# can.net
KiCad netlist of a schematic drawn in Altium Designer
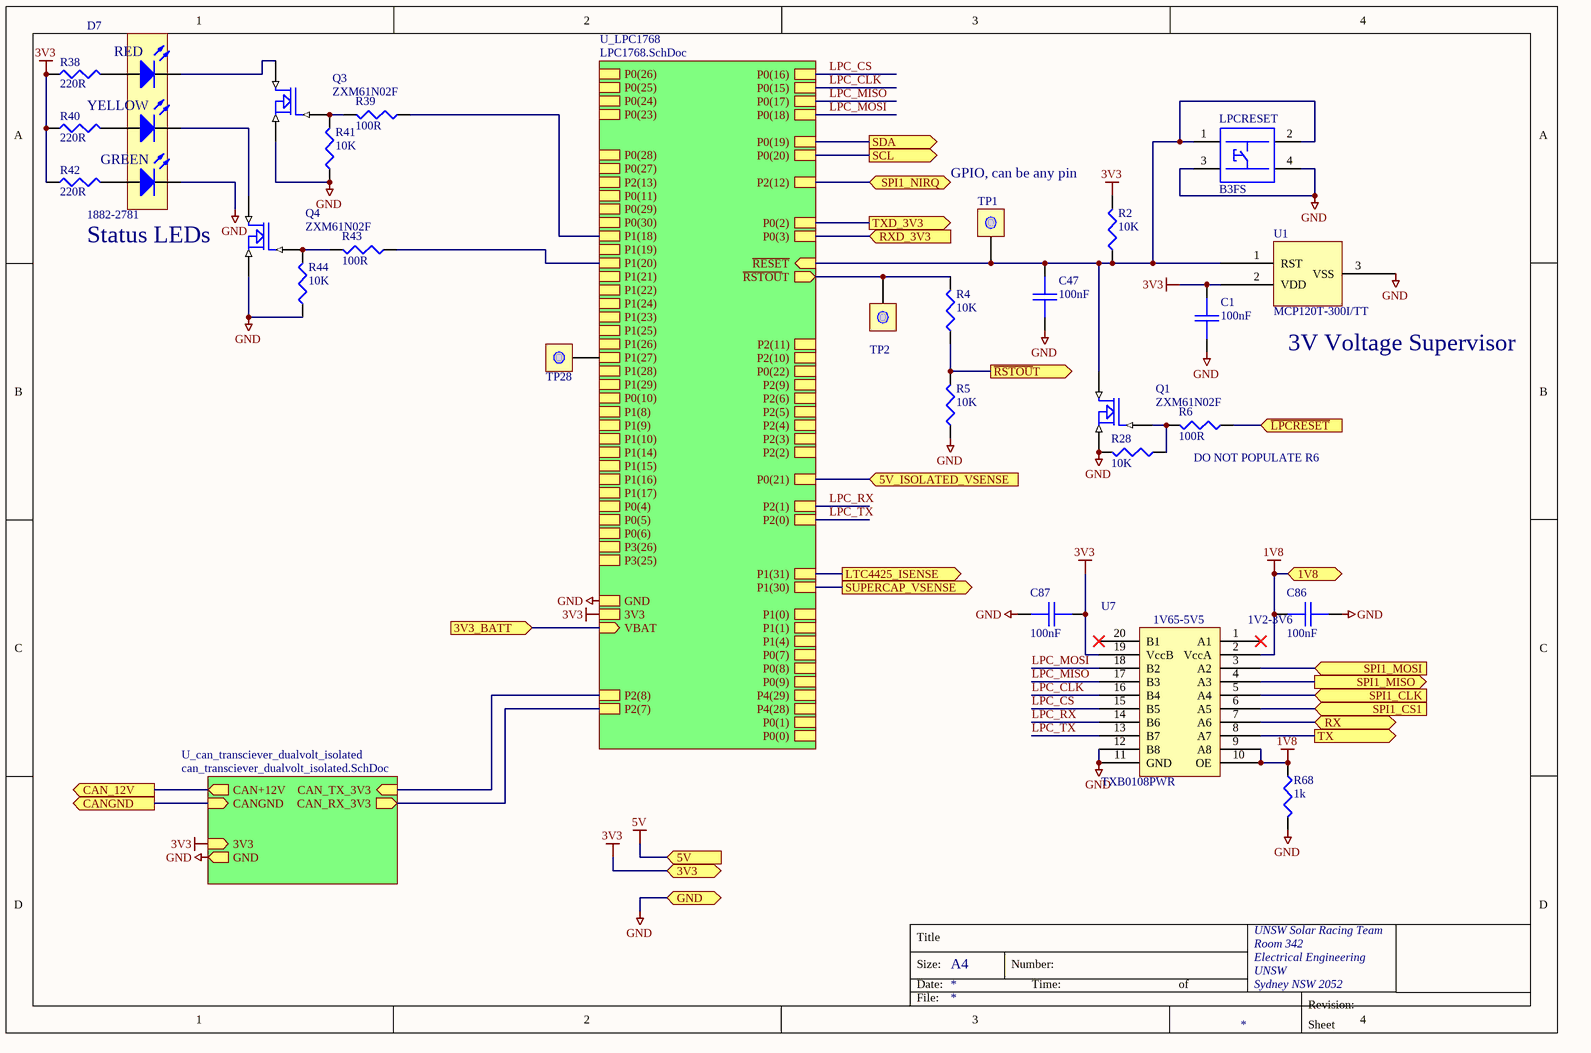
[diagram p0: can.SchDoc]

(export (version "E")
  (design (tool "Eeschema 10.0.6"))
  (components
    (comp (ref "C1")
      (value "100nF")
      (footprint "0603")
      (description "Capacitor")
      (libsource (lib "RCLDQ") (part "CAP"))
    )
    (comp (ref "C47")
      (value "100nF")
      (footprint "0603")
      (description "Capacitor")
      (libsource (lib "RCLDQ") (part "CAP"))
    )
    (comp (ref "C86")
      (value "100nF")
      (footprint "0603")
      (description "Capacitor")
      (libsource (lib "RCLDQ") (part "CAP"))
    )
    (comp (ref "C87")
      (value "100nF")
      (footprint "0603")
      (description "Capacitor")
      (libsource (lib "RCLDQ") (part "CAP"))
    )
    (comp (ref "D7")
      (value "1882-2781")
      (footprint "LED_TRILEVEL")
      (description "Three level LED")
      (libsource (lib "RCLDQ") (part "LED-TRILEVEL"))
    )
    (comp (ref "LPCRESET")
      (value "B3FS")
      (footprint "B3FS-1052")
      (description "SMD tactile switch")
      (libsource (lib "Miscellaneous") (part "B3FS"))
    )
    (comp (ref "Q1")
      (value "ZXM61N02F")
      (footprint "SOT23-3")
      (description "1.7A, 20V N-Channel Enhancement mode FET")
      (libsource (lib "RCLDQ") (part "ZXM61N02F"))
    )
    (comp (ref "Q3")
      (value "ZXM61N02F")
      (footprint "SOT23-3")
      (description "1.7A, 20V N-Channel Enhancement mode FET")
      (libsource (lib "RCLDQ") (part "ZXM61N02F"))
    )
    (comp (ref "Q4")
      (value "ZXM61N02F")
      (footprint "SOT23-3")
      (description "1.7A, 20V N-Channel Enhancement mode FET")
      (libsource (lib "RCLDQ") (part "ZXM61N02F"))
    )
    (comp (ref "R2")
      (value "10K")
      (footprint "0603")
      (description "Resistor")
      (libsource (lib "RCLDQ") (part "RES1"))
    )
    (comp (ref "R4")
      (value "10K")
      (footprint "0603")
      (description "Resistor")
      (libsource (lib "RCLDQ") (part "RES1"))
    )
    (comp (ref "R5")
      (value "10K")
      (footprint "0603")
      (description "Resistor")
      (libsource (lib "RCLDQ") (part "RES1"))
    )
    (comp (ref "R6")
      (value "100R")
      (footprint "0603")
      (description "Resistor")
      (libsource (lib "RCLDQ") (part "RES1"))
    )
    (comp (ref "R28")
      (value "10K")
      (footprint "0603")
      (description "Resistor")
      (libsource (lib "RCLDQ") (part "RES1"))
    )
    (comp (ref "R38")
      (value "220R")
      (footprint "0603")
      (description "Resistor")
      (libsource (lib "RCLDQ") (part "RES1"))
    )
    (comp (ref "R39")
      (value "100R")
      (footprint "0603")
      (description "Resistor")
      (libsource (lib "RCLDQ") (part "RES1"))
    )
    (comp (ref "R40")
      (value "220R")
      (footprint "0603")
      (description "Resistor")
      (libsource (lib "RCLDQ") (part "RES1"))
    )
    (comp (ref "R41")
      (value "10K")
      (footprint "0603")
      (description "Resistor")
      (libsource (lib "RCLDQ") (part "RES1"))
    )
    (comp (ref "R42")
      (value "220R")
      (footprint "0603")
      (description "Resistor")
      (libsource (lib "RCLDQ") (part "RES1"))
    )
    (comp (ref "R43")
      (value "100R")
      (footprint "0603")
      (description "Resistor")
      (libsource (lib "RCLDQ") (part "RES1"))
    )
    (comp (ref "R44")
      (value "10K")
      (footprint "0603")
      (description "Resistor")
      (libsource (lib "RCLDQ") (part "RES1"))
    )
    (comp (ref "R68")
      (value "1k")
      (footprint "0603")
      (description "Resistor")
      (libsource (lib "RCLDQ") (part "RES1"))
    )
    (comp (ref "TP1")
      (value "RESET")
      (footprint "TESTPOINT")
      (description "TEST POINT")
      (libsource (lib "Miscellaneous") (part "TEST"))
    )
    (comp (ref "TP2")
      (value "RSTOUT")
      (footprint "TESTPOINT")
      (description "TEST POINT")
      (libsource (lib "") (part "TEST_1"))
    )
    (comp (ref "TP28")
      (value "CLKOUT")
      (footprint "TESTPOINT")
      (description "TEST POINT")
      (libsource (lib "") (part "TEST_2"))
    )
    (comp (ref "U1")
      (value "MCP120T-300I/TT")
      (footprint "SOT23-3")
      (description "Voltage Supervisor")
      (libsource (lib "sion") (part "MCP120T"))
    )
    (comp (ref "U7")
      (value "TXB0108PWR")
      (footprint "TSSOP20")
      (description "4 bit bidirectional auto direction sense level translator")
      (libsource (lib "sion") (part "TXB0108PWR"))
    )
  )
  (nets
    (net (code "7") (name "/LPC_CLK") (class "Default")
      (node (ref "U7") (pin "16") (pinfunction "B4_16") (pintype "passive"))
    )
    (net (code "8") (name "/LPC_CS") (class "Default")
      (node (ref "U7") (pin "15") (pinfunction "B5_15") (pintype "passive"))
    )
    (net (code "9") (name "/LPC_MISO") (class "Default")
      (node (ref "U7") (pin "17") (pinfunction "B3_17") (pintype "passive"))
    )
    (net (code "10") (name "/LPC_MOSI") (class "Default")
      (node (ref "U7") (pin "18") (pinfunction "B2_18") (pintype "passive"))
    )
    (net (code "11") (name "/LPC_RX") (class "Default")
      (node (ref "U7") (pin "14") (pinfunction "B6_14") (pintype "power_in"))
    )
    (net (code "12") (name "/LPC_TX") (class "Default")
      (node (ref "U7") (pin "13") (pinfunction "B7_13") (pintype "passive"))
    )
    (net (code "43") (name "/P1(18)") (class "Default")
      (node (ref "R39") (pin "1") (pinfunction "1_1") (pintype "passive"))
    )
    (net (code "45") (name "/P1(20)") (class "Default")
      (node (ref "R43") (pin "1") (pinfunction "1_1") (pintype "passive"))
    )
    (net (code "52") (name "/P1(27)") (class "Default")
      (node (ref "TP28") (pin "0") (pinfunction "TP_0") (pintype "passive"))
    )
    (net (code "68") (name "/RX") (class "Default")
      (node (ref "U7") (pin "7") (pinfunction "A6_7") (pintype "power_in"))
    )
    (net (code "72") (name "/SPI1_CLK") (class "Default")
      (node (ref "U7") (pin "5") (pinfunction "A4_5") (pintype "passive"))
    )
    (net (code "73") (name "/SPI1_CS1") (class "Default")
      (node (ref "U7") (pin "6") (pinfunction "A5_6") (pintype "passive"))
    )
    (net (code "74") (name "/SPI1_MISO") (class "Default")
      (node (ref "U7") (pin "4") (pinfunction "A3_4") (pintype "passive"))
    )
    (net (code "75") (name "/SPI1_MOSI") (class "Default")
      (node (ref "U7") (pin "3") (pinfunction "A2_3") (pintype "passive"))
    )
    (net (code "78") (name "/TX") (class "Default")
      (node (ref "U7") (pin "8") (pinfunction "A7_8") (pintype "passive"))
    )
    (net (code "80") (name "/~{LPCRESET}") (class "Default")
      (node (ref "R6") (pin "2") (pinfunction "2_2") (pintype "passive"))
    )
    (net (code "81") (name "/~{RESET}") (class "Default")
      (node (ref "C47") (pin "1") (pinfunction "1_1") (pintype "passive"))
      (node (ref "LPCRESET") (pin "1") (pinfunction "A1_1") (pintype "passive"))
      (node (ref "LPCRESET") (pin "2") (pinfunction "A2_2") (pintype "passive"))
      (node (ref "Q1") (pin "3") (pinfunction "D_3") (pintype "input"))
      (node (ref "R2") (pin "1") (pinfunction "1_1") (pintype "passive"))
      (node (ref "TP1") (pin "0") (pinfunction "TP_0") (pintype "passive"))
      (node (ref "U1") (pin "1") (pinfunction "RST_1") (pintype "passive"))
    )
    (net (code "82") (name "/~{RSTOU}T") (class "Default")
      (node (ref "R4") (pin "1") (pinfunction "1_1") (pintype "passive"))
      (node (ref "R5") (pin "2") (pinfunction "2_2") (pintype "passive"))
    )
    (net (code "83") (name "/~{RSTOU}T_1") (class "Default")
      (node (ref "R4") (pin "2") (pinfunction "2_2") (pintype "passive"))
      (node (ref "TP2") (pin "0") (pinfunction "TP_0") (pintype "passive"))
    )
    (net (code "84") (name "1V8") (class "Default")
      (node (ref "C86") (pin "2") (pinfunction "2_2") (pintype "passive"))
      (node (ref "R68") (pin "2") (pinfunction "2_2") (pintype "passive"))
      (node (ref "U7") (pin "10") (pinfunction "OE_10") (pintype "passive"))
      (node (ref "U7") (pin "2") (pinfunction "VccA_2") (pintype "power_in"))
      (node (ref "U7") (pin "9") (pinfunction "A8_9") (pintype "passive"))
    )
    (net (code "85") (name "3V3") (class "Default")
      (node (ref "C1") (pin "1") (pinfunction "1_1") (pintype "passive"))
      (node (ref "C87") (pin "1") (pinfunction "1_1") (pintype "passive"))
      (node (ref "R2") (pin "2") (pinfunction "2_2") (pintype "passive"))
      (node (ref "R38") (pin "1") (pinfunction "1_1") (pintype "passive"))
      (node (ref "R40") (pin "1") (pinfunction "1_1") (pintype "passive"))
      (node (ref "R42") (pin "1") (pinfunction "1_1") (pintype "passive"))
      (node (ref "U1") (pin "2") (pinfunction "VDD_2") (pintype "passive"))
      (node (ref "U7") (pin "19") (pinfunction "VccB_19") (pintype "passive"))
    )
    (net (code "87") (name "GND") (class "Default")
      (node (ref "C1") (pin "2") (pinfunction "2_2") (pintype "passive"))
      (node (ref "C47") (pin "2") (pinfunction "2_2") (pintype "passive"))
      (node (ref "C86") (pin "1") (pinfunction "1_1") (pintype "passive"))
      (node (ref "C87") (pin "2") (pinfunction "2_2") (pintype "passive"))
      (node (ref "D7") (pin "1") (pinfunction "K_1") (pintype "passive"))
      (node (ref "LPCRESET") (pin "3") (pinfunction "B2_3") (pintype "passive"))
      (node (ref "LPCRESET") (pin "4") (pinfunction "B1_4") (pintype "passive"))
      (node (ref "Q1") (pin "2") (pinfunction "S_2") (pintype "input"))
      (node (ref "Q3") (pin "2") (pinfunction "S_2") (pintype "input"))
      (node (ref "Q4") (pin "2") (pinfunction "S_2") (pintype "input"))
      (node (ref "R28") (pin "2") (pinfunction "2_2") (pintype "passive"))
      (node (ref "R41") (pin "1") (pinfunction "1_1") (pintype "passive"))
      (node (ref "R44") (pin "1") (pinfunction "1_1") (pintype "passive"))
      (node (ref "R5") (pin "1") (pinfunction "1_1") (pintype "passive"))
      (node (ref "R68") (pin "1") (pinfunction "1_1") (pintype "passive"))
      (node (ref "U1") (pin "3") (pinfunction "VSS_3") (pintype "passive"))
      (node (ref "U7") (pin "11") (pinfunction "GND_11") (pintype "passive"))
      (node (ref "U7") (pin "12") (pinfunction "B8_12") (pintype "passive"))
    )
    (net (code "88") (name "Net-(D7-A-Pad4)") (class "Default")
      (node (ref "D7") (pin "4") (pinfunction "A_4") (pintype "passive"))
      (node (ref "R38") (pin "2") (pinfunction "2_2") (pintype "passive"))
    )
    (net (code "89") (name "Net-(D7-A-Pad5)") (class "Default")
      (node (ref "D7") (pin "5") (pinfunction "A_5") (pintype "passive"))
      (node (ref "R40") (pin "2") (pinfunction "2_2") (pintype "passive"))
    )
    (net (code "90") (name "Net-(D7-A-Pad6)") (class "Default")
      (node (ref "D7") (pin "6") (pinfunction "A_6") (pintype "passive"))
      (node (ref "R42") (pin "2") (pinfunction "2_2") (pintype "passive"))
    )
    (net (code "91") (name "Net-(Q1-G)") (class "Default")
      (node (ref "Q1") (pin "1") (pinfunction "G_1") (pintype "input"))
      (node (ref "R28") (pin "1") (pinfunction "1_1") (pintype "passive"))
      (node (ref "R6") (pin "1") (pinfunction "1_1") (pintype "passive"))
    )
    (net (code "92") (name "Net-(Q3-D)") (class "Default")
      (node (ref "D7") (pin "3") (pinfunction "K_3") (pintype "passive"))
      (node (ref "Q3") (pin "3") (pinfunction "D_3") (pintype "input"))
    )
    (net (code "93") (name "Net-(Q3-G)") (class "Default")
      (node (ref "Q3") (pin "1") (pinfunction "G_1") (pintype "input"))
      (node (ref "R39") (pin "2") (pinfunction "2_2") (pintype "passive"))
      (node (ref "R41") (pin "2") (pinfunction "2_2") (pintype "passive"))
    )
    (net (code "94") (name "Net-(Q4-D)") (class "Default")
      (node (ref "D7") (pin "2") (pinfunction "K_2") (pintype "passive"))
      (node (ref "Q4") (pin "3") (pinfunction "D_3") (pintype "input"))
    )
    (net (code "95") (name "Net-(Q4-G)") (class "Default")
      (node (ref "Q4") (pin "1") (pinfunction "G_1") (pintype "input"))
      (node (ref "R43") (pin "2") (pinfunction "2_2") (pintype "passive"))
      (node (ref "R44") (pin "2") (pinfunction "2_2") (pintype "passive"))
    )
    (net (code "96") (name "unconnected-(U7-A1-Pad1)") (class "Default")
      (node (ref "U7") (pin "1") (pinfunction "A1_1") (pintype "passive+no_connect"))
    )
    (net (code "97") (name "unconnected-(U7-B1-Pad20)") (class "Default")
      (node (ref "U7") (pin "20") (pinfunction "B1_20") (pintype "passive+no_connect"))
    )
  )
)
